# PowerSupply.net
KiCad netlist of a schematic drawn in Altium Designer
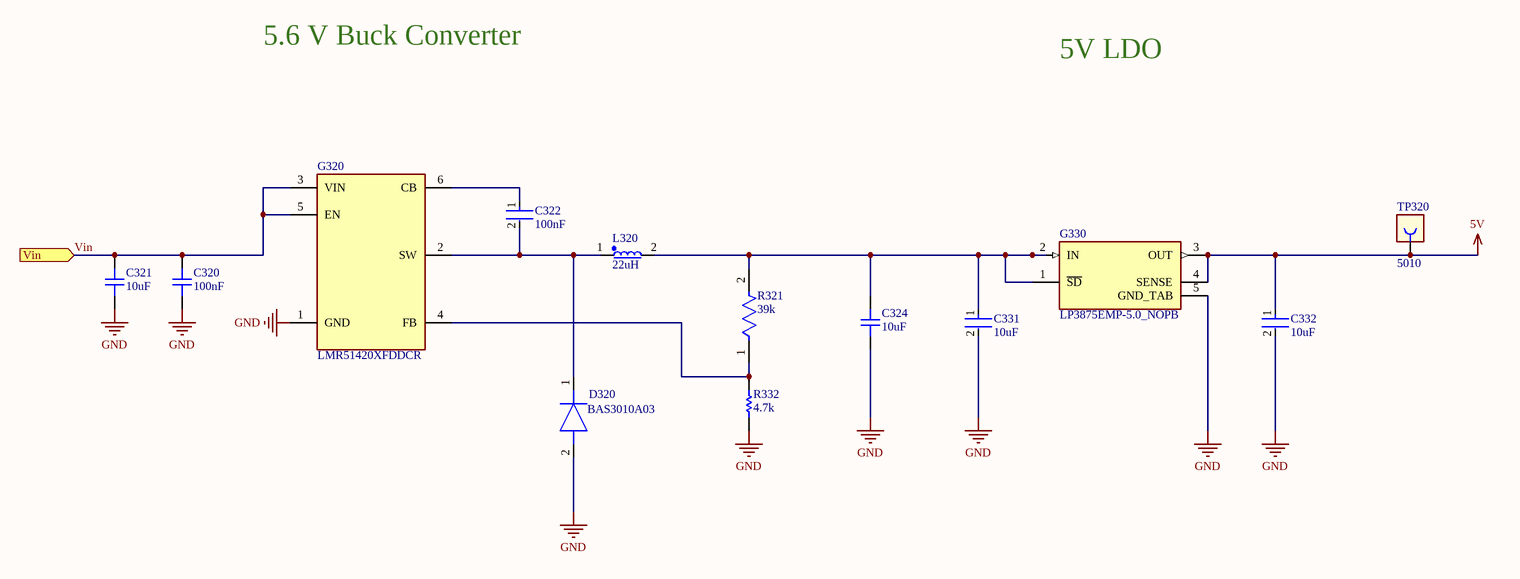
[diagram p0: PowerSupply.SchDoc]

(export (version "E")
  (design (tool "Eeschema 10.0.6"))
  (components
    (comp (ref "C320")
      (value "100nF")
      (footprint "CAPC3216X125N-0")
      (description "CAP / CERA / 100nF / 50V / 10% / X7R (EIA) / -55°C to 125°C / 1206(3216) / SMD / -")
      (fields (field (name "LEGACY PARTNUMBER") "CAP01005660") (field (name "MANUFACTURER") "MuRata"))
      (libsource (lib "PCBLibraryData") (part "CAP-SGL-STD-02P_00000001"))
    )
    (comp (ref "C321")
      (value "10uF")
      (footprint "CAPC3216X190N-1")
      (description "CAP / CERA / 10uF / 50V / 20% / X5R (EIA) / -55°C to 85°C / 1206 (3216) / SMD / -")
      (fields (field (name "MANUFACTURER") "Taiyo Yuden"))
      (libsource (lib "PCBLibraryData") (part "CAP-SGL-STD-02P_00000001"))
    )
    (comp (ref "C322")
      (value "100nF")
      (footprint "FP-1206-L_3_2_0_2-W_1_6_0-MFG")
      (description "General Purpose Ceramic Capacitor, 1206, 100nF, 10%, X7R, 15%, 50V")
      (fields (field (name "TOLERANCE") "10%") (field (name "VOLTAGE") "50V"))
      (libsource (lib "Altium Content Vault") (part "02cd4be3c70576c341d710602a673aa"))
    )
    (comp (ref "C324")
      (value "10uF")
      (footprint "CAPC3216X190N-1")
      (description "CAP / CERA / 10uF / 50V / 20% / X5R (EIA) / -55°C to 85°C / 1206 (3216) / SMD / -")
      (fields (field (name "MANUFACTURER") "Taiyo Yuden"))
      (libsource (lib "PCBLibraryData") (part "CAP-SGL-STD-02P_00000001"))
    )
    (comp (ref "C331")
      (value "10uF")
      (footprint "FP-1206-L_3_2_0_3-W_1_6_0-IPC_B")
      (description "None")
      (fields (field (name "TOLERANCE") "20%"))
      (libsource (lib "Altium Content Vault") (part "11868f565c42a9108669ba33697ecf6"))
    )
    (comp (ref "C332")
      (value "10uF")
      (footprint "FP-1206-L_3_2_0_3-W_1_6_0-IPC_B")
      (description "None")
      (fields (field (name "TOLERANCE") "20%"))
      (libsource (lib "Altium Content Vault") (part "11868f565c42a9108669ba33697ecf6"))
    )
    (comp (ref "D320")
      (value "BAS3010A03")
      (footprint "myPcbLib:SOD2513X110N")
      (description "Diode")
      (fields
        (field (name "MANUFACTURER_PART_NUMBER") "BAS3010A03WE6327HTSA1")
        (field (name "MOUSER PART NUMBER") "726-BAS3010A-03WE6")
      )
      (libsource (lib "mySchlib") (part "BAS3010A03WE6327HTSA1"))
    )
    (comp (ref "G320")
      (value "LMR51420XFDDCR")
      (footprint "myPcbLib:SOT95P280X110-6N")
      (description "Integrated Circuit")
      (fields
        (field (name "MOUSER PART NUMBER") "595-LMR51420XFDDCR")
        (field (name "LCSC PART #") "C5752071")
      )
      (libsource (lib "mySchlib") (part "LMR51420XFDDCR"))
    )
    (comp (ref "G330")
      (value "LP3875EMP-5.0_NOPB")
      (footprint "myPcbLib:SOT150P700X180-5N")
      (description "Integrated Circuit")
      (fields
        (field (name "MANUFACTURER_PART_NUMBER") "LP3875EMP-5.0/NOPB")
        (field (name "MOUSER PART NUMBER") "926-3875EMP-5.0/NOPB")
      )
      (libsource (lib "mySchlib") (part "LP3875EMP-5.0_NOPB"))
    )
    (comp (ref "L320")
      (value "22uH")
      (footprint "IND-SMD-74404064220")
      (fields
        (field (name "MANUFACTURER") "Wurth Elektronik")
        (field (name "LCSC PART #") "C1331921")
        (field (name "MPN") "74404064220")
      )
      (libsource (lib "PCBLibraryData") (part "IND-SGL-STD-WDG-COR-02P_0000002B"))
    )
    (comp (ref "R321")
      (value "39k")
      (footprint "FP-CRCW1206-e3-IPC_A")
      (description "RES Thick Film, 39kΩ, 1%, 0.25W, 100ppm/°C, 1206")
      (fields (field (name "TOLERANCE") "1%") (field (name "MPN") "CRCW120639K0FKEA"))
      (libsource (lib "Altium Content Vault") (part "1029c3af85768c4190bb7ad29bc67b5"))
    )
    (comp (ref "R332")
      (value "4.7k")
      (footprint "RESC3216X60X45ML15T20")
      (description "Chip Resistor, 4.7 KOhm, +/- 1%, 0.25 W, -55 to 155 degC, 1206 (3216 Metric), RoHS, Tape and Reel")
      (fields (field (name "MANUFACTURER") "Vishay Semiconductor") (field (name "TOLERANCE") "1%"))
      (libsource (lib "Altium Content Vault") (part "RES-2"))
    )
    (comp (ref "TP320")
      (value "5010")
      (footprint "CON-THT-TP-5010")
      (description "PC Test Point-Multipurpose THT, Red")
      (fields
        (field (name "LEGACY PARTNUMBER") "CON01500529")
        (field (name "MANUFACTURER") "Keystone Electronics Corp.")
      )
      (libsource (lib "PCBLibraryData") (part "connector_1_f"))
    )
  )
  (nets
    (net (code "1") (name "/Vin") (class "Default")
      (node (ref "C320") (pin "2") (pinfunction "2_2") (pintype "passive"))
      (node (ref "C321") (pin "2") (pinfunction "2_2") (pintype "passive"))
      (node (ref "G320") (pin "3") (pinfunction "VIN_3") (pintype "passive"))
      (node (ref "G320") (pin "5") (pinfunction "EN_5") (pintype "passive"))
    )
    (net (code "2") (name "5V") (class "Default")
      (node (ref "C332") (pin "1") (pinfunction "1_1") (pintype "passive"))
      (node (ref "G330") (pin "3") (pinfunction "OUT_3") (pintype "output"))
      (node (ref "G330") (pin "4") (pinfunction "SENSE_4") (pintype "passive"))
      (node (ref "TP320") (pin "1") (pinfunction "1_1") (pintype "passive"))
    )
    (net (code "3") (name "GND") (class "Default")
      (node (ref "C320") (pin "1") (pinfunction "1_1") (pintype "passive"))
      (node (ref "C321") (pin "1") (pinfunction "1_1") (pintype "passive"))
      (node (ref "C324") (pin "1") (pinfunction "1_1") (pintype "passive"))
      (node (ref "C331") (pin "2") (pinfunction "2_2") (pintype "passive"))
      (node (ref "C332") (pin "2") (pinfunction "2_2") (pintype "passive"))
      (node (ref "D320") (pin "2") (pinfunction "A_2") (pintype "passive"))
      (node (ref "G320") (pin "1") (pinfunction "GND_1") (pintype "passive"))
      (node (ref "G330") (pin "5") (pinfunction "GND_TAB_5") (pintype "power_in"))
      (node (ref "R332") (pin "1") (pinfunction "1_1") (pintype "passive"))
    )
    (net (code "4") (name "Net-(D320-K)") (class "Default")
      (node (ref "C322") (pin "2") (pinfunction "2_2") (pintype "passive"))
      (node (ref "D320") (pin "1") (pinfunction "K_1") (pintype "passive"))
      (node (ref "G320") (pin "2") (pinfunction "SW_2") (pintype "passive"))
      (node (ref "L320") (pin "1") (pinfunction "1_1") (pintype "passive"))
    )
    (net (code "5") (name "Net-(G320-CB)") (class "Default")
      (node (ref "C322") (pin "1") (pinfunction "1_1") (pintype "passive"))
      (node (ref "G320") (pin "6") (pinfunction "CB_6") (pintype "passive"))
    )
    (net (code "6") (name "Net-(G320-FB)") (class "Default")
      (node (ref "G320") (pin "4") (pinfunction "FB_4") (pintype "passive"))
      (node (ref "R321") (pin "1") (pinfunction "1_1") (pintype "passive"))
      (node (ref "R332") (pin "2") (pinfunction "2_2") (pintype "passive"))
    )
    (net (code "7") (name "Net-(G330-IN)") (class "Default")
      (node (ref "C324") (pin "2") (pinfunction "2_2") (pintype "passive"))
      (node (ref "C331") (pin "1") (pinfunction "1_1") (pintype "passive"))
      (node (ref "G330") (pin "1") (pinfunction "~{SD}_1") (pintype "passive"))
      (node (ref "G330") (pin "2") (pinfunction "IN_2") (pintype "input"))
      (node (ref "L320") (pin "2") (pinfunction "2_2") (pintype "passive"))
      (node (ref "R321") (pin "2") (pinfunction "2_2") (pintype "passive"))
    )
  )
)
